# PaxInstruments-T100.net
KiCad netlist of a schematic drawn in EAGLE
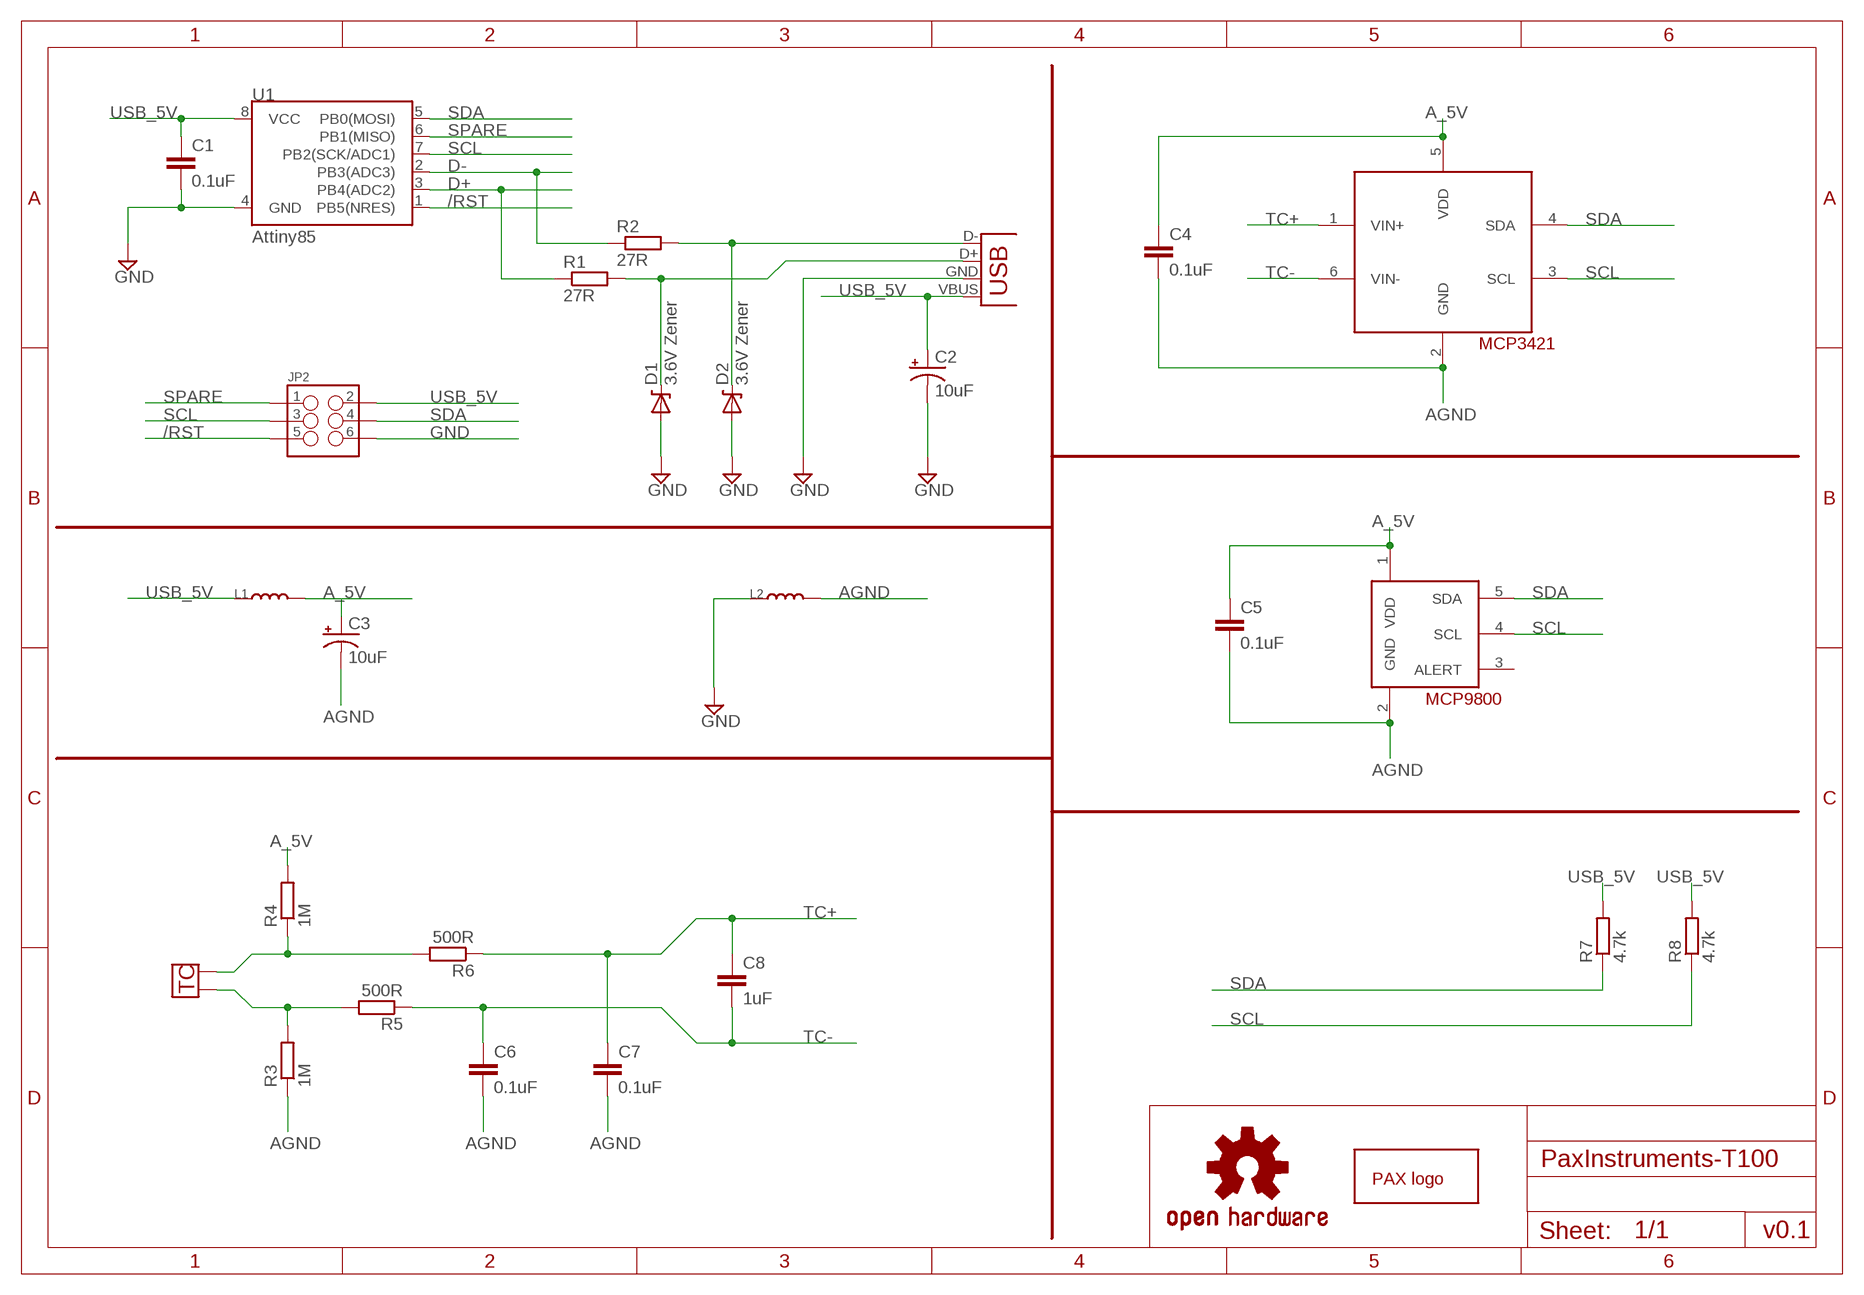
[diagram p0: schematic, sheet 1]

(export (version "E")
  (design (tool "Eeschema 10.0.6"))
  (components
    (comp (ref "C1")
      (value "0.1uF")
      (footprint "eagle-import:C0603")
      (libsource (lib "eagle-import") (part "C-EUC0603"))
    )
    (comp (ref "C2")
      (value "10uF")
      (footprint "eagle-import:EIA3216")
      (libsource (lib "eagle-import") (part "10UF-TANT"))
    )
    (comp (ref "C3")
      (value "10uF")
      (footprint "eagle-import:EIA3216")
      (libsource (lib "eagle-import") (part "10UF-TANT"))
    )
    (comp (ref "C4")
      (value "0.1uF")
      (footprint "eagle-import:C0603")
      (libsource (lib "eagle-import") (part "C-EUC0603"))
    )
    (comp (ref "C5")
      (value "0.1uF")
      (footprint "eagle-import:C0603")
      (libsource (lib "eagle-import") (part "C-EUC0603"))
    )
    (comp (ref "C6")
      (value "0.1uF")
      (footprint "eagle-import:C0603")
      (libsource (lib "eagle-import") (part "C-EUC0603"))
    )
    (comp (ref "C7")
      (value "0.1uF")
      (footprint "eagle-import:C0603")
      (libsource (lib "eagle-import") (part "C-EUC0603"))
    )
    (comp (ref "C8")
      (value "1uF")
      (footprint "eagle-import:C0603")
      (libsource (lib "eagle-import") (part "C-EUC0603"))
    )
    (comp (ref "D1")
      (value "3.6V Zener")
      (footprint "eagle-import:SOD-323")
      (libsource (lib "eagle-import") (part "DIODE-ZENER-BZT52"))
    )
    (comp (ref "D2")
      (value "3.6V Zener")
      (footprint "eagle-import:SOD-323")
      (libsource (lib "eagle-import") (part "DIODE-ZENER-BZT52"))
    )
    (comp (ref "JP1")
      (value "USB-A-H")
      (footprint "eagle-import:USB-A-H")
      (libsource (lib "eagle-import") (part "USB-A-H"))
    )
    (comp (ref "JP2")
      (value "M03X2SMT")
      (footprint "eagle-import:2X3_SMT_POSTS")
      (libsource (lib "eagle-import") (part "M03X2SMT"))
    )
    (comp (ref "L1")
      (value "L-0603")
      (footprint "eagle-import:L0603")
      (libsource (lib "eagle-import") (part "L-0603"))
    )
    (comp (ref "L2")
      (value "L-0603")
      (footprint "eagle-import:L0603")
      (libsource (lib "eagle-import") (part "L-0603"))
    )
    (comp (ref "LOGO1")
      (value "OSHW-LOGOS")
      (footprint "eagle-import:OSHW-LOGO-S")
      (libsource (lib "eagle-import") (part "OSHW-LOGOS"))
    )
    (comp (ref "R1")
      (value "27R")
      (footprint "eagle-import:R0603")
      (libsource (lib "eagle-import") (part "R-EU_R0603"))
    )
    (comp (ref "R2")
      (value "27R")
      (footprint "eagle-import:R0603")
      (libsource (lib "eagle-import") (part "R-EU_R0603"))
    )
    (comp (ref "R3")
      (value "1M")
      (footprint "eagle-import:R0603")
      (libsource (lib "eagle-import") (part "R-EU_R0603"))
    )
    (comp (ref "R4")
      (value "1M")
      (footprint "eagle-import:R0603")
      (libsource (lib "eagle-import") (part "R-EU_R0603"))
    )
    (comp (ref "R5")
      (value "500R")
      (footprint "eagle-import:R0603")
      (libsource (lib "eagle-import") (part "R-EU_R0603"))
    )
    (comp (ref "R6")
      (value "500R")
      (footprint "eagle-import:R0603")
      (libsource (lib "eagle-import") (part "R-EU_R0603"))
    )
    (comp (ref "R7")
      (value "4.7k")
      (footprint "eagle-import:R0603")
      (libsource (lib "eagle-import") (part "R-EU_R0603"))
    )
    (comp (ref "R8")
      (value "4.7k")
      (footprint "eagle-import:R0603")
      (libsource (lib "eagle-import") (part "R-EU_R0603"))
    )
    (comp (ref "U$1")
      (value "PAX-LOGO")
      (footprint "eagle-import:PAX-LOGO")
      (libsource (lib "eagle-import") (part "PAX-LOGO"))
    )
    (comp (ref "U$2")
      (value "TC-MINI-CONNECTOR")
      (footprint "eagle-import:TC-MINI-CONNECTOR")
      (libsource (lib "eagle-import") (part "TC-MINI-CONNECTOR"))
    )
    (comp (ref "U$3")
      (value "MCP3421")
      (footprint "eagle-import:SOT23-6")
      (libsource (lib "eagle-import") (part "MCP3421"))
    )
    (comp (ref "U$4")
      (value "MCP9800")
      (footprint "eagle-import:SOT23-5")
      (libsource (lib "eagle-import") (part "MCP9800"))
    )
    (comp (ref "U1")
      (value "Attiny85")
      (footprint "eagle-import:SO08-EIAJ")
      (libsource (lib "eagle-import") (part "ATTINY45TINY45-20-SMT"))
    )
  )
  (nets
    (net (code "1") (name "/AGND") (class "Default")
      (node (ref "C3") (pin "C") (pinfunction "-_C") (pintype "passive"))
      (node (ref "C4") (pin "2") (pinfunction "2_2") (pintype "passive"))
      (node (ref "C5") (pin "2") (pinfunction "2_2") (pintype "passive"))
      (node (ref "C6") (pin "2") (pinfunction "2_2") (pintype "passive"))
      (node (ref "C7") (pin "2") (pinfunction "2_2") (pintype "passive"))
      (node (ref "L2") (pin "2") (pinfunction "2_2") (pintype "passive"))
      (node (ref "R3") (pin "1") (pinfunction "1_1") (pintype "passive"))
      (node (ref "U$3") (pin "2") (pinfunction "GND_2") (pintype "bidirectional"))
      (node (ref "U$4") (pin "2") (pinfunction "GND_2") (pintype "bidirectional"))
    )
    (net (code "2") (name "/A_5V") (class "Default")
      (node (ref "C3") (pin "A") (pinfunction "+_A") (pintype "passive"))
      (node (ref "C4") (pin "1") (pinfunction "1_1") (pintype "passive"))
      (node (ref "C5") (pin "1") (pinfunction "1_1") (pintype "passive"))
      (node (ref "L1") (pin "2") (pinfunction "2_2") (pintype "passive"))
      (node (ref "R4") (pin "2") (pinfunction "2_2") (pintype "passive"))
      (node (ref "U$3") (pin "5") (pinfunction "VDD_5") (pintype "bidirectional"))
      (node (ref "U$4") (pin "1") (pinfunction "VDD_1") (pintype "bidirectional"))
    )
    (net (code "3") (name "/D+") (class "Default")
      (node (ref "R1") (pin "1") (pinfunction "1_1") (pintype "passive"))
      (node (ref "U1") (pin "3") (pinfunction "PB4(ADC2)_3") (pintype "bidirectional"))
    )
    (net (code "4") (name "/D-") (class "Default")
      (node (ref "R2") (pin "1") (pinfunction "1_1") (pintype "passive"))
      (node (ref "U1") (pin "2") (pinfunction "PB3(ADC3)_2") (pintype "bidirectional"))
    )
    (net (code "5") (name "/SCL") (class "Default")
      (node (ref "JP2") (pin "3") (pinfunction "3_3") (pintype "bidirectional"))
      (node (ref "R8") (pin "1") (pinfunction "1_1") (pintype "passive"))
      (node (ref "U$3") (pin "3") (pinfunction "SCL_3") (pintype "bidirectional"))
      (node (ref "U$4") (pin "4") (pinfunction "SCL_4") (pintype "bidirectional"))
      (node (ref "U1") (pin "7") (pinfunction "PB2(SCK/ADC1)_7") (pintype "bidirectional"))
    )
    (net (code "6") (name "/SDA") (class "Default")
      (node (ref "JP2") (pin "4") (pinfunction "4_4") (pintype "bidirectional"))
      (node (ref "R7") (pin "1") (pinfunction "1_1") (pintype "passive"))
      (node (ref "U$3") (pin "4") (pinfunction "SDA_4") (pintype "bidirectional"))
      (node (ref "U$4") (pin "5") (pinfunction "SDA_5") (pintype "bidirectional"))
      (node (ref "U1") (pin "5") (pinfunction "PB0(MOSI)_5") (pintype "bidirectional"))
    )
    (net (code "7") (name "/SPARE") (class "Default")
      (node (ref "JP2") (pin "1") (pinfunction "1_1") (pintype "bidirectional"))
      (node (ref "U1") (pin "6") (pinfunction "PB1(MISO)_6") (pintype "bidirectional"))
    )
    (net (code "8") (name "/TC+") (class "Default")
      (node (ref "C7") (pin "1") (pinfunction "1_1") (pintype "passive"))
      (node (ref "C8") (pin "1") (pinfunction "1_1") (pintype "passive"))
      (node (ref "R6") (pin "1") (pinfunction "1_1") (pintype "passive"))
      (node (ref "U$3") (pin "1") (pinfunction "VIN+_1") (pintype "bidirectional"))
    )
    (net (code "9") (name "/TC-") (class "Default")
      (node (ref "C6") (pin "1") (pinfunction "1_1") (pintype "passive"))
      (node (ref "C8") (pin "2") (pinfunction "2_2") (pintype "passive"))
      (node (ref "R5") (pin "1") (pinfunction "1_1") (pintype "passive"))
      (node (ref "U$3") (pin "6") (pinfunction "VIN-_6") (pintype "bidirectional"))
    )
    (net (code "10") (name "/USB_5V") (class "Default")
      (node (ref "C1") (pin "1") (pinfunction "1_1") (pintype "passive"))
      (node (ref "C2") (pin "A") (pinfunction "+_A") (pintype "passive"))
      (node (ref "JP1") (pin "VBUS") (pinfunction "GND_VBUS") (pintype "bidirectional"))
      (node (ref "JP2") (pin "2") (pinfunction "2_2") (pintype "bidirectional"))
      (node (ref "L1") (pin "1") (pinfunction "1_1") (pintype "passive"))
      (node (ref "R7") (pin "2") (pinfunction "2_2") (pintype "passive"))
      (node (ref "R8") (pin "2") (pinfunction "2_2") (pintype "passive"))
      (node (ref "U1") (pin "8") (pinfunction "VCC_8") (pintype "bidirectional"))
    )
    (net (code "11") (name "/{slash}RST") (class "Default")
      (node (ref "JP2") (pin "5") (pinfunction "5_5") (pintype "bidirectional"))
      (node (ref "U1") (pin "1") (pinfunction "PB5(NRES)_1") (pintype "bidirectional"))
    )
    (net (code "12") (name "GND") (class "Default")
      (node (ref "C1") (pin "2") (pinfunction "2_2") (pintype "passive"))
      (node (ref "C2") (pin "C") (pinfunction "-_C") (pintype "passive"))
      (node (ref "D1") (pin "2") (pinfunction "A_2") (pintype "passive"))
      (node (ref "D2") (pin "2") (pinfunction "A_2") (pintype "passive"))
      (node (ref "JP1") (pin "GND") (pinfunction "VBUS_GND") (pintype "bidirectional"))
      (node (ref "JP2") (pin "6") (pinfunction "6_6") (pintype "bidirectional"))
      (node (ref "L2") (pin "1") (pinfunction "1_1") (pintype "passive"))
      (node (ref "U1") (pin "4") (pinfunction "GND_4") (pintype "bidirectional"))
    )
    (net (code "13") (name "Net-(D1-C)") (class "Default")
      (node (ref "D1") (pin "1") (pinfunction "C_1") (pintype "passive"))
      (node (ref "JP1") (pin "D+") (pinfunction "D-_D+") (pintype "bidirectional"))
      (node (ref "R1") (pin "2") (pinfunction "2_2") (pintype "passive"))
    )
    (net (code "14") (name "Net-(D2-C)") (class "Default")
      (node (ref "D2") (pin "1") (pinfunction "C_1") (pintype "passive"))
      (node (ref "JP1") (pin "D-") (pinfunction "D+_D-") (pintype "bidirectional"))
      (node (ref "R2") (pin "2") (pinfunction "2_2") (pintype "passive"))
    )
    (net (code "15") (name "Net-(R3-Pad2)") (class "Default")
      (node (ref "R3") (pin "2") (pinfunction "2_2") (pintype "passive"))
      (node (ref "R5") (pin "2") (pinfunction "2_2") (pintype "passive"))
      (node (ref "U$2") (pin "P$2") (pinfunction "P$2_P$2") (pintype "bidirectional"))
    )
    (net (code "16") (name "Net-(R4-Pad1)") (class "Default")
      (node (ref "R4") (pin "1") (pinfunction "1_1") (pintype "passive"))
      (node (ref "R6") (pin "2") (pinfunction "2_2") (pintype "passive"))
      (node (ref "U$2") (pin "P$1") (pinfunction "P$1_P$1") (pintype "bidirectional"))
    )
    (net (code "17") (name "unconnected-(U$4-ALERT-Pad3)") (class "Default")
      (node (ref "U$4") (pin "3") (pinfunction "ALERT_3") (pintype "bidirectional"))
    )
  )
)
